# Breadboard_Amp.net
KiCad netlist of a schematic drawn in EAGLE
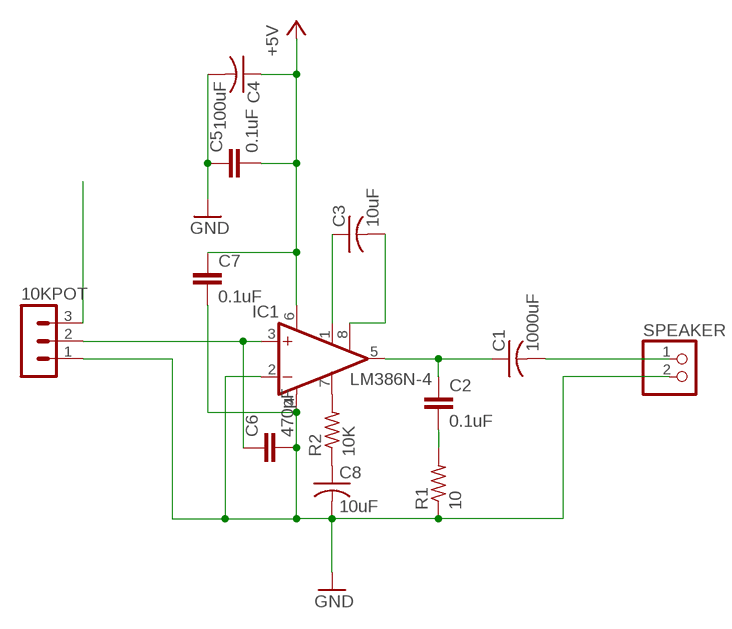
[diagram p0: schematic, sheet 1]

(export (version "E")
  (design (tool "Eeschema 10.0.6"))
  (components
    (comp (ref "10KPOT")
      (value "MA03-1")
      (footprint "eagle-import:MA03-1")
      (libsource (lib "eagle-import") (part "MA03-1"))
    )
    (comp (ref "C1")
      (value "1000uF")
      (footprint "eagle-import:C025-030X050")
      (libsource (lib "eagle-import") (part "C-US025-030X050"))
    )
    (comp (ref "C2")
      (value "0.1uF")
      (footprint "eagle-import:C2.5-4")
      (libsource (lib "eagle-import") (part "C2.5/4"))
    )
    (comp (ref "C3")
      (value "10uF")
      (footprint "eagle-import:C025-030X050")
      (libsource (lib "eagle-import") (part "C-US025-030X050"))
    )
    (comp (ref "C4")
      (value "100uF")
      (footprint "eagle-import:C025-030X050")
      (libsource (lib "eagle-import") (part "C-US025-030X050"))
    )
    (comp (ref "C5")
      (value "0.1uF")
      (footprint "eagle-import:C2.5-4")
      (libsource (lib "eagle-import") (part "C2.5/4"))
    )
    (comp (ref "C6")
      (value "470pF")
      (footprint "eagle-import:C2.5-4")
      (libsource (lib "eagle-import") (part "C2.5/4"))
    )
    (comp (ref "C7")
      (value "0.1uF")
      (footprint "eagle-import:C2.5-4")
      (libsource (lib "eagle-import") (part "C2.5/4"))
    )
    (comp (ref "C8")
      (value "10uF")
      (footprint "eagle-import:C025-030X050")
      (libsource (lib "eagle-import") (part "C-US025-030X050"))
    )
    (comp (ref "IC1")
      (value "LM386N-4")
      (footprint "eagle-import:DIL08")
      (libsource (lib "eagle-import") (part "LM386?-N4"))
    )
    (comp (ref "R1")
      (value "10")
      (footprint "eagle-import:0207_7")
      (libsource (lib "eagle-import") (part "R-US_0207/7"))
    )
    (comp (ref "R2")
      (value "10K")
      (footprint "eagle-import:0207_7")
      (libsource (lib "eagle-import") (part "R-US_0207/7"))
    )
    (comp (ref "SPEAKER")
      (value "PINHD-1X2")
      (footprint "eagle-import:1X02")
      (libsource (lib "eagle-import") (part "PINHD-1X2"))
    )
  )
  (nets
    (net (code "1") (name "+5V") (class "Default")
      (node (ref "C4") (pin "1") (pinfunction "1_1") (pintype "passive"))
      (node (ref "C5") (pin "2") (pinfunction "2_2") (pintype "passive"))
      (node (ref "C7") (pin "1") (pinfunction "1_1") (pintype "passive"))
      (node (ref "IC1") (pin "6") (pinfunction "VS_6") (pintype "power_in"))
    )
    (net (code "2") (name "GND") (class "Default")
      (node (ref "10KPOT") (pin "1") (pinfunction "1_1") (pintype "passive"))
      (node (ref "C4") (pin "2") (pinfunction "2_2") (pintype "passive"))
      (node (ref "C5") (pin "1") (pinfunction "1_1") (pintype "passive"))
      (node (ref "C6") (pin "2") (pinfunction "2_2") (pintype "passive"))
      (node (ref "C7") (pin "2") (pinfunction "2_2") (pintype "passive"))
      (node (ref "C8") (pin "2") (pinfunction "2_2") (pintype "passive"))
      (node (ref "IC1") (pin "2") (pinfunction "-IN_2") (pintype "input"))
      (node (ref "IC1") (pin "4") (pinfunction "GND_4") (pintype "power_in"))
      (node (ref "R1") (pin "1") (pinfunction "1_1") (pintype "passive"))
      (node (ref "SPEAKER") (pin "2") (pinfunction "2_2") (pintype "passive"))
    )
    (net (code "3") (name "Net-(C1-Pad2)") (class "Default")
      (node (ref "C1") (pin "2") (pinfunction "2_2") (pintype "passive"))
      (node (ref "SPEAKER") (pin "1") (pinfunction "1_1") (pintype "passive"))
    )
    (net (code "4") (name "Net-(C2-Pad2)") (class "Default")
      (node (ref "C2") (pin "2") (pinfunction "2_2") (pintype "passive"))
      (node (ref "R1") (pin "2") (pinfunction "2_2") (pintype "passive"))
    )
    (net (code "5") (name "Net-(C3-Pad1)") (class "Default")
      (node (ref "C3") (pin "1") (pinfunction "1_1") (pintype "passive"))
      (node (ref "IC1") (pin "1") (pinfunction "GAIN_1") (pintype "passive"))
    )
    (net (code "6") (name "Net-(C3-Pad2)") (class "Default")
      (node (ref "C3") (pin "2") (pinfunction "2_2") (pintype "passive"))
      (node (ref "IC1") (pin "8") (pinfunction "GAIN_8") (pintype "passive"))
    )
    (net (code "7") (name "Net-(C8-Pad1)") (class "Default")
      (node (ref "C8") (pin "1") (pinfunction "1_1") (pintype "passive"))
      (node (ref "R2") (pin "1") (pinfunction "1_1") (pintype "passive"))
    )
    (net (code "8") (name "Net-(IC1-+IN)") (class "Default")
      (node (ref "10KPOT") (pin "2") (pinfunction "2_2") (pintype "passive"))
      (node (ref "C6") (pin "1") (pinfunction "1_1") (pintype "passive"))
      (node (ref "IC1") (pin "3") (pinfunction "+IN_3") (pintype "input"))
    )
    (net (code "9") (name "Net-(IC1-BYPASS)") (class "Default")
      (node (ref "IC1") (pin "7") (pinfunction "BYPASS_7") (pintype "passive"))
      (node (ref "R2") (pin "2") (pinfunction "2_2") (pintype "passive"))
    )
    (net (code "10") (name "Net-(IC1-OUT)") (class "Default")
      (node (ref "C1") (pin "1") (pinfunction "1_1") (pintype "passive"))
      (node (ref "C2") (pin "1") (pinfunction "1_1") (pintype "passive"))
      (node (ref "IC1") (pin "5") (pinfunction "OUT_5") (pintype "output"))
    )
    (net (code "11") (name "unconnected-(10KPOT-Pad3)") (class "Default")
      (node (ref "10KPOT") (pin "3") (pinfunction "3_3") (pintype "passive"))
    )
  )
)
